# 03_MotorStage_v1.net
KiCad netlist of a schematic drawn in EAGLE
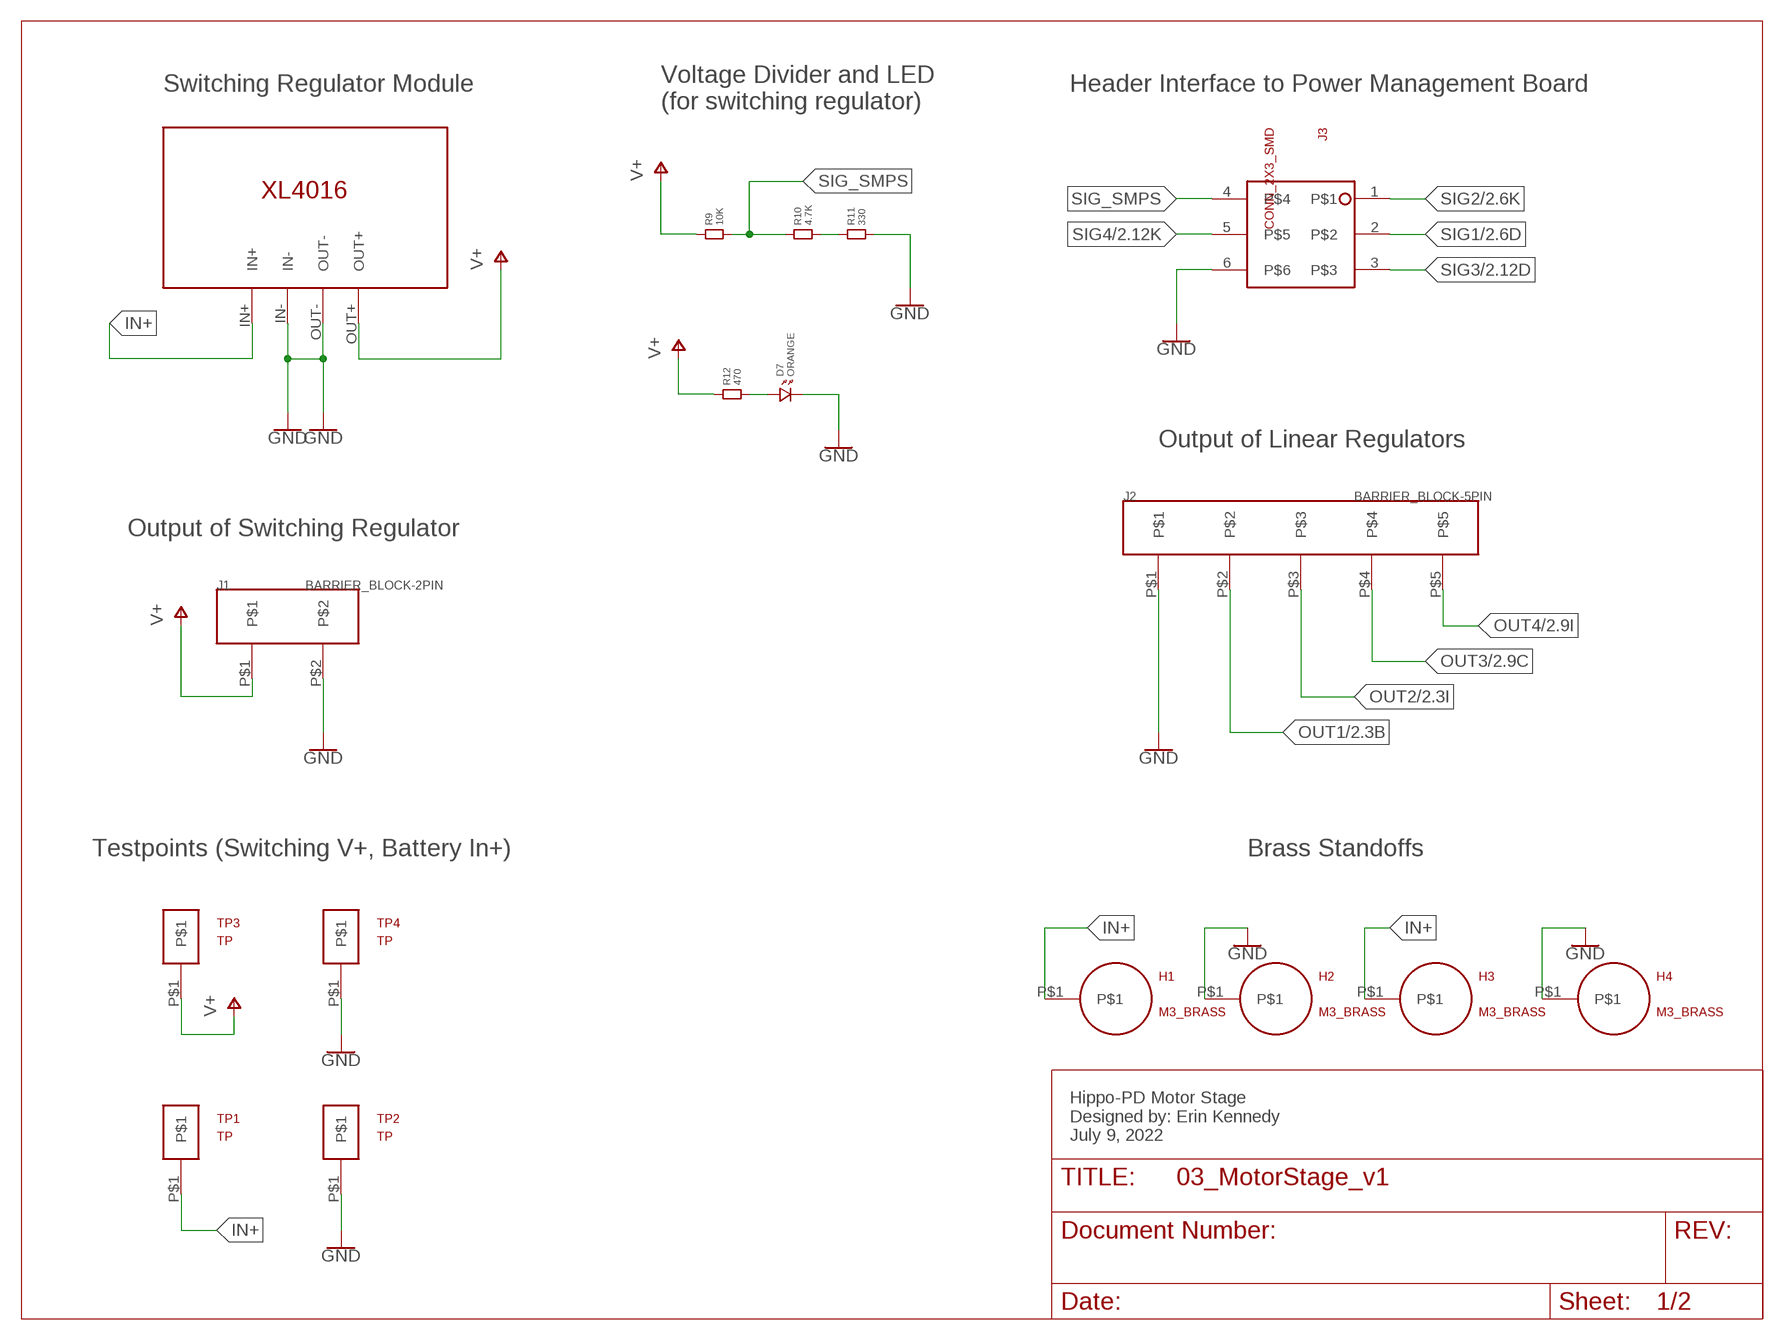
[diagram p0: schematic, sheet 1]
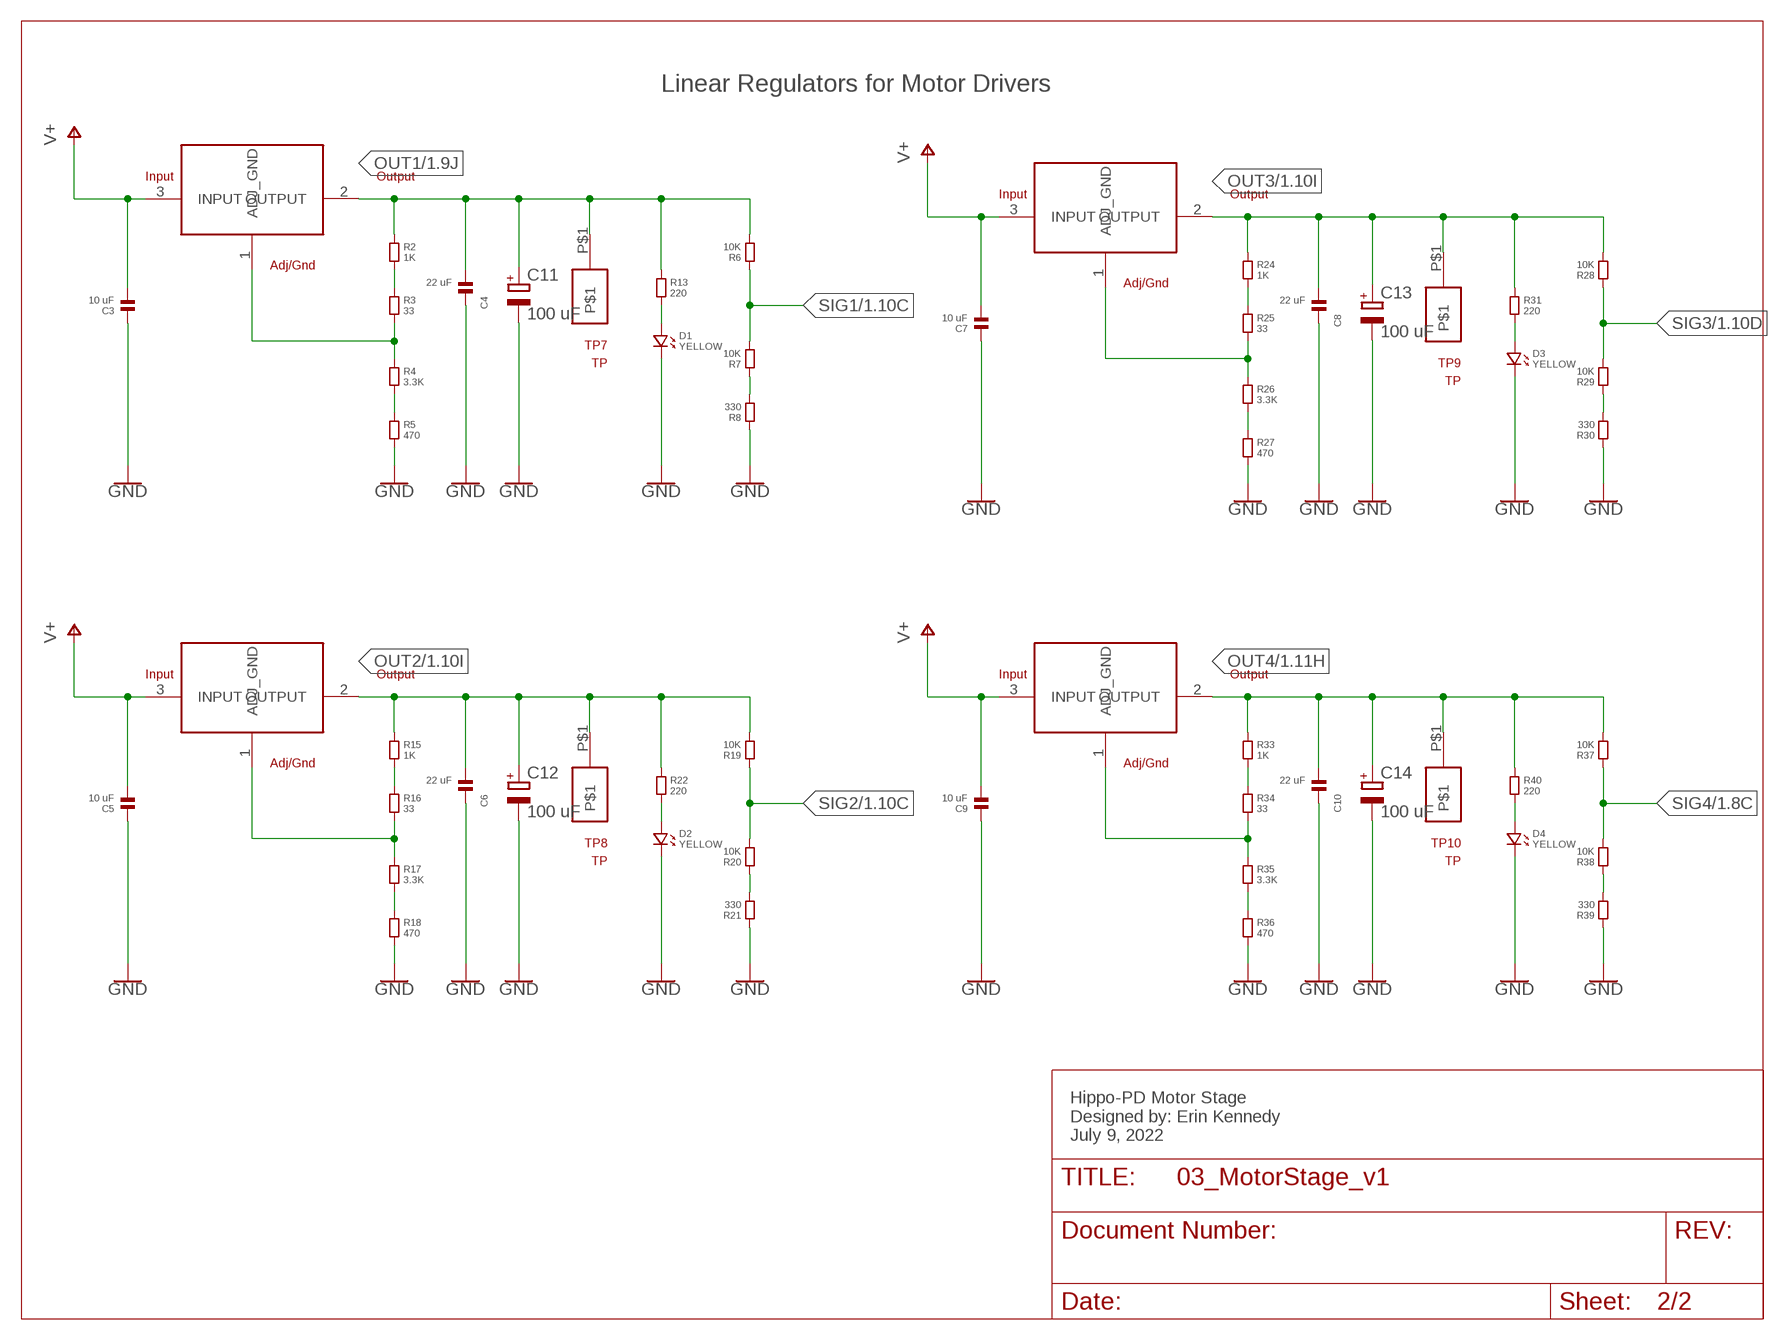
[diagram p1: schematic, sheet 2]

(export (version "E")
  (design (tool "Eeschema 10.0.6"))
  (components
    (comp (ref "C3")
      (value "10 uF")
      (footprint "eagle-import:1206")
      (libsource (lib "eagle-import") (part "CAPACITOR.1206"))
    )
    (comp (ref "C4")
      (value "22 uF")
      (footprint "eagle-import:1206")
      (libsource (lib "eagle-import") (part "CAPACITOR.1206"))
    )
    (comp (ref "C5")
      (value "10 uF")
      (footprint "eagle-import:1206")
      (libsource (lib "eagle-import") (part "CAPACITOR.1206"))
    )
    (comp (ref "C6")
      (value "22 uF")
      (footprint "eagle-import:1206")
      (libsource (lib "eagle-import") (part "CAPACITOR.1206"))
    )
    (comp (ref "C7")
      (value "10 uF")
      (footprint "eagle-import:1206")
      (libsource (lib "eagle-import") (part "CAPACITOR.1206"))
    )
    (comp (ref "C8")
      (value "22 uF")
      (footprint "eagle-import:1206")
      (libsource (lib "eagle-import") (part "CAPACITOR.1206"))
    )
    (comp (ref "C9")
      (value "10 uF")
      (footprint "eagle-import:1206")
      (libsource (lib "eagle-import") (part "CAPACITOR.1206"))
    )
    (comp (ref "C10")
      (value "22 uF")
      (footprint "eagle-import:1206")
      (libsource (lib "eagle-import") (part "CAPACITOR.1206"))
    )
    (comp (ref "C11")
      (value "100 uF")
      (footprint "eagle-import:ELECTROLYTIC_CAP")
      (fields (field (name "MF") "Wurth Electronics") (field (name "MP") "865080545012"))
      (libsource (lib "eagle-import") (part "ELECTROLYTIC_CAP"))
    )
    (comp (ref "C12")
      (value "100 uF")
      (footprint "eagle-import:ELECTROLYTIC_CAP")
      (fields (field (name "MF") "Wurth Electronics") (field (name "MP") "865080545012"))
      (libsource (lib "eagle-import") (part "ELECTROLYTIC_CAP"))
    )
    (comp (ref "C13")
      (value "100 uF")
      (footprint "eagle-import:ELECTROLYTIC_CAP")
      (fields (field (name "MF") "Wurth Electronics") (field (name "MP") "865080545012"))
      (libsource (lib "eagle-import") (part "ELECTROLYTIC_CAP"))
    )
    (comp (ref "C14")
      (value "100 uF")
      (footprint "eagle-import:ELECTROLYTIC_CAP")
      (fields (field (name "MF") "Wurth Electronics") (field (name "MP") "865080545012"))
      (libsource (lib "eagle-import") (part "ELECTROLYTIC_CAP"))
    )
    (comp (ref "D1")
      (value "YELLOW")
      (footprint "eagle-import:1206.LED")
      (libsource (lib "eagle-import") (part "LED.1206"))
    )
    (comp (ref "D2")
      (value "YELLOW")
      (footprint "eagle-import:1206.LED")
      (libsource (lib "eagle-import") (part "LED.1206"))
    )
    (comp (ref "D3")
      (value "YELLOW")
      (footprint "eagle-import:1206.LED")
      (libsource (lib "eagle-import") (part "LED.1206"))
    )
    (comp (ref "D4")
      (value "YELLOW")
      (footprint "eagle-import:1206.LED")
      (libsource (lib "eagle-import") (part "LED.1206"))
    )
    (comp (ref "R2")
      (value "1K")
      (footprint "eagle-import:1206")
      (libsource (lib "eagle-import") (part "RESISTOR.1206"))
    )
    (comp (ref "R3")
      (value "33")
      (footprint "eagle-import:1206")
      (libsource (lib "eagle-import") (part "RESISTOR.1206"))
    )
    (comp (ref "R4")
      (value "3.3K")
      (footprint "eagle-import:1206")
      (libsource (lib "eagle-import") (part "RESISTOR.1206"))
    )
    (comp (ref "R5")
      (value "470")
      (footprint "eagle-import:1206")
      (libsource (lib "eagle-import") (part "RESISTOR.1206"))
    )
    (comp (ref "R6")
      (value "10K")
      (footprint "eagle-import:1206")
      (libsource (lib "eagle-import") (part "RESISTOR.1206"))
    )
    (comp (ref "R7")
      (value "10K")
      (footprint "eagle-import:1206")
      (libsource (lib "eagle-import") (part "RESISTOR.1206"))
    )
    (comp (ref "R8")
      (value "330")
      (footprint "eagle-import:1206")
      (libsource (lib "eagle-import") (part "RESISTOR.1206"))
    )
    (comp (ref "R13")
      (value "220")
      (footprint "eagle-import:1206")
      (libsource (lib "eagle-import") (part "RESISTOR.1206"))
    )
    (comp (ref "R15")
      (value "1K")
      (footprint "eagle-import:1206")
      (libsource (lib "eagle-import") (part "RESISTOR.1206"))
    )
    (comp (ref "R16")
      (value "33")
      (footprint "eagle-import:1206")
      (libsource (lib "eagle-import") (part "RESISTOR.1206"))
    )
    (comp (ref "R17")
      (value "3.3K")
      (footprint "eagle-import:1206")
      (libsource (lib "eagle-import") (part "RESISTOR.1206"))
    )
    (comp (ref "R18")
      (value "470")
      (footprint "eagle-import:1206")
      (libsource (lib "eagle-import") (part "RESISTOR.1206"))
    )
    (comp (ref "R19")
      (value "10K")
      (footprint "eagle-import:1206")
      (libsource (lib "eagle-import") (part "RESISTOR.1206"))
    )
    (comp (ref "R20")
      (value "10K")
      (footprint "eagle-import:1206")
      (libsource (lib "eagle-import") (part "RESISTOR.1206"))
    )
    (comp (ref "R21")
      (value "330")
      (footprint "eagle-import:1206")
      (libsource (lib "eagle-import") (part "RESISTOR.1206"))
    )
    (comp (ref "R22")
      (value "220")
      (footprint "eagle-import:1206")
      (libsource (lib "eagle-import") (part "RESISTOR.1206"))
    )
    (comp (ref "R24")
      (value "1K")
      (footprint "eagle-import:1206")
      (libsource (lib "eagle-import") (part "RESISTOR.1206"))
    )
    (comp (ref "R25")
      (value "33")
      (footprint "eagle-import:1206")
      (libsource (lib "eagle-import") (part "RESISTOR.1206"))
    )
    (comp (ref "R26")
      (value "3.3K")
      (footprint "eagle-import:1206")
      (libsource (lib "eagle-import") (part "RESISTOR.1206"))
    )
    (comp (ref "R27")
      (value "470")
      (footprint "eagle-import:1206")
      (libsource (lib "eagle-import") (part "RESISTOR.1206"))
    )
    (comp (ref "R28")
      (value "10K")
      (footprint "eagle-import:1206")
      (libsource (lib "eagle-import") (part "RESISTOR.1206"))
    )
    (comp (ref "R29")
      (value "10K")
      (footprint "eagle-import:1206")
      (libsource (lib "eagle-import") (part "RESISTOR.1206"))
    )
    (comp (ref "R30")
      (value "330")
      (footprint "eagle-import:1206")
      (libsource (lib "eagle-import") (part "RESISTOR.1206"))
    )
    (comp (ref "R31")
      (value "220")
      (footprint "eagle-import:1206")
      (libsource (lib "eagle-import") (part "RESISTOR.1206"))
    )
    (comp (ref "R33")
      (value "1K")
      (footprint "eagle-import:1206")
      (libsource (lib "eagle-import") (part "RESISTOR.1206"))
    )
    (comp (ref "R34")
      (value "33")
      (footprint "eagle-import:1206")
      (libsource (lib "eagle-import") (part "RESISTOR.1206"))
    )
    (comp (ref "R35")
      (value "3.3K")
      (footprint "eagle-import:1206")
      (libsource (lib "eagle-import") (part "RESISTOR.1206"))
    )
    (comp (ref "R36")
      (value "470")
      (footprint "eagle-import:1206")
      (libsource (lib "eagle-import") (part "RESISTOR.1206"))
    )
    (comp (ref "R37")
      (value "10K")
      (footprint "eagle-import:1206")
      (libsource (lib "eagle-import") (part "RESISTOR.1206"))
    )
    (comp (ref "R38")
      (value "10K")
      (footprint "eagle-import:1206")
      (libsource (lib "eagle-import") (part "RESISTOR.1206"))
    )
    (comp (ref "R39")
      (value "330")
      (footprint "eagle-import:1206")
      (libsource (lib "eagle-import") (part "RESISTOR.1206"))
    )
    (comp (ref "R40")
      (value "220")
      (footprint "eagle-import:1206")
      (libsource (lib "eagle-import") (part "RESISTOR.1206"))
    )
    (comp (ref "TP7") (value "TP") (footprint "eagle-import:TP") (libsource (lib "eagle-import") (part "TP")))
    (comp (ref "TP8") (value "TP") (footprint "eagle-import:TP") (libsource (lib "eagle-import") (part "TP")))
    (comp (ref "TP9") (value "TP") (footprint "eagle-import:TP") (libsource (lib "eagle-import") (part "TP")))
    (comp (ref "TP10")
      (value "TP")
      (footprint "eagle-import:TP")
      (libsource (lib "eagle-import") (part "TP"))
    )
    (comp (ref "U2")
      (value "AZ1084C")
      (footprint "eagle-import:AZ1084C")
      (libsource (lib "eagle-import") (part "AZ1084C"))
    )
    (comp (ref "U3")
      (value "AZ1084C")
      (footprint "eagle-import:AZ1084C")
      (libsource (lib "eagle-import") (part "AZ1084C"))
    )
    (comp (ref "U4")
      (value "AZ1084C")
      (footprint "eagle-import:AZ1084C")
      (libsource (lib "eagle-import") (part "AZ1084C"))
    )
    (comp (ref "U5")
      (value "AZ1084C")
      (footprint "eagle-import:AZ1084C")
      (libsource (lib "eagle-import") (part "AZ1084C"))
    )
    (comp (ref "D7")
      (value "ORANGE")
      (footprint "eagle-import:1206.LED")
      (libsource (lib "eagle-import") (part "LED.1206"))
    )
    (comp (ref "H1")
      (value "M3_BRASS")
      (footprint "eagle-import:M3_BRASS")
      (libsource (lib "eagle-import") (part "M3_BRASS"))
    )
    (comp (ref "H2")
      (value "M3_BRASS")
      (footprint "eagle-import:M3_BRASS")
      (libsource (lib "eagle-import") (part "M3_BRASS"))
    )
    (comp (ref "H3")
      (value "M3_BRASS")
      (footprint "eagle-import:M3_BRASS")
      (libsource (lib "eagle-import") (part "M3_BRASS"))
    )
    (comp (ref "H4")
      (value "M3_BRASS")
      (footprint "eagle-import:M3_BRASS")
      (libsource (lib "eagle-import") (part "M3_BRASS"))
    )
    (comp (ref "J1")
      (value "BARRIER_BLOCK-2PIN")
      (footprint "eagle-import:BARRIERBLOCK-2PIN")
      (libsource (lib "eagle-import") (part "BARRIER_BLOCK-2PIN"))
    )
    (comp (ref "J2")
      (value "BARRIER_BLOCK-5PIN")
      (footprint "eagle-import:BARRIERBLOCK-5PIN")
      (libsource (lib "eagle-import") (part "BARRIER_BLOCK-5PIN"))
    )
    (comp (ref "J3")
      (value "CONN_2X3_SMD")
      (footprint "eagle-import:2X3_SMD_CONNECTOR")
      (libsource (lib "eagle-import") (part "CONN_2X3_SMD"))
    )
    (comp (ref "R9")
      (value "10K")
      (footprint "eagle-import:1206")
      (libsource (lib "eagle-import") (part "RESISTOR.1206"))
    )
    (comp (ref "R10")
      (value "4.7K")
      (footprint "eagle-import:1206")
      (libsource (lib "eagle-import") (part "RESISTOR.1206"))
    )
    (comp (ref "R11")
      (value "330")
      (footprint "eagle-import:1206")
      (libsource (lib "eagle-import") (part "RESISTOR.1206"))
    )
    (comp (ref "R12")
      (value "470")
      (footprint "eagle-import:1206")
      (libsource (lib "eagle-import") (part "RESISTOR.1206"))
    )
    (comp (ref "TP1") (value "TP") (footprint "eagle-import:TP") (libsource (lib "eagle-import") (part "TP")))
    (comp (ref "TP2") (value "TP") (footprint "eagle-import:TP") (libsource (lib "eagle-import") (part "TP")))
    (comp (ref "TP3") (value "TP") (footprint "eagle-import:TP") (libsource (lib "eagle-import") (part "TP")))
    (comp (ref "TP4") (value "TP") (footprint "eagle-import:TP") (libsource (lib "eagle-import") (part "TP")))
    (comp (ref "U1")
      (value "XL4016-DEV")
      (footprint "eagle-import:XL4016-DEV")
      (libsource (lib "eagle-import") (part "XL4016-DEV"))
    )
  )
  (nets
    (net (code "1") (name "GND") (class "Default")
      (node (ref "C10") (pin "1") (pinfunction "1_1") (pintype "bidirectional"))
      (node (ref "C11") (pin "-") (pinfunction "-_-") (pintype "passive"))
      (node (ref "C12") (pin "-") (pinfunction "-_-") (pintype "passive"))
      (node (ref "C13") (pin "-") (pinfunction "-_-") (pintype "passive"))
      (node (ref "C14") (pin "-") (pinfunction "-_-") (pintype "passive"))
      (node (ref "C3") (pin "1") (pinfunction "1_1") (pintype "bidirectional"))
      (node (ref "C4") (pin "1") (pinfunction "1_1") (pintype "bidirectional"))
      (node (ref "C5") (pin "1") (pinfunction "1_1") (pintype "bidirectional"))
      (node (ref "C6") (pin "1") (pinfunction "1_1") (pintype "bidirectional"))
      (node (ref "C7") (pin "1") (pinfunction "1_1") (pintype "bidirectional"))
      (node (ref "C8") (pin "1") (pinfunction "1_1") (pintype "bidirectional"))
      (node (ref "C9") (pin "1") (pinfunction "1_1") (pintype "bidirectional"))
      (node (ref "D1") (pin "P$2") (pinfunction "2_P$2") (pintype "bidirectional"))
      (node (ref "D2") (pin "P$2") (pinfunction "2_P$2") (pintype "bidirectional"))
      (node (ref "D3") (pin "P$2") (pinfunction "2_P$2") (pintype "bidirectional"))
      (node (ref "D4") (pin "P$2") (pinfunction "2_P$2") (pintype "bidirectional"))
      (node (ref "D7") (pin "P$2") (pinfunction "2_P$2") (pintype "bidirectional"))
      (node (ref "H2") (pin "P$1") (pinfunction "P$1_P$1") (pintype "bidirectional"))
      (node (ref "H4") (pin "P$1") (pinfunction "P$1_P$1") (pintype "bidirectional"))
      (node (ref "J1") (pin "P$2") (pinfunction "P$2_P$2") (pintype "bidirectional"))
      (node (ref "J2") (pin "P$1") (pinfunction "P$1_P$1") (pintype "bidirectional"))
      (node (ref "J3") (pin "6") (pinfunction "P$6_6") (pintype "bidirectional"))
      (node (ref "R11") (pin "2") (pinfunction "2_2") (pintype "bidirectional"))
      (node (ref "R18") (pin "2") (pinfunction "2_2") (pintype "bidirectional"))
      (node (ref "R21") (pin "1") (pinfunction "1_1") (pintype "bidirectional"))
      (node (ref "R27") (pin "2") (pinfunction "2_2") (pintype "bidirectional"))
      (node (ref "R30") (pin "1") (pinfunction "1_1") (pintype "bidirectional"))
      (node (ref "R36") (pin "2") (pinfunction "2_2") (pintype "bidirectional"))
      (node (ref "R39") (pin "1") (pinfunction "1_1") (pintype "bidirectional"))
      (node (ref "R5") (pin "2") (pinfunction "2_2") (pintype "bidirectional"))
      (node (ref "R8") (pin "1") (pinfunction "1_1") (pintype "bidirectional"))
      (node (ref "TP2") (pin "P$1") (pinfunction "P$1_P$1") (pintype "bidirectional"))
      (node (ref "TP4") (pin "P$1") (pinfunction "P$1_P$1") (pintype "bidirectional"))
      (node (ref "U1") (pin "IN-") (pinfunction "IN-_IN-") (pintype "bidirectional"))
      (node (ref "U1") (pin "OUT-") (pinfunction "OUT-_OUT-") (pintype "bidirectional"))
    )
    (net (code "2") (name "IN+") (class "Default")
      (node (ref "H1") (pin "P$1") (pinfunction "P$1_P$1") (pintype "bidirectional"))
      (node (ref "H3") (pin "P$1") (pinfunction "P$1_P$1") (pintype "bidirectional"))
      (node (ref "TP1") (pin "P$1") (pinfunction "P$1_P$1") (pintype "bidirectional"))
      (node (ref "U1") (pin "IN+") (pinfunction "IN+_IN+") (pintype "bidirectional"))
    )
    (net (code "3") (name "Net-(D1-1)") (class "Default")
      (node (ref "D1") (pin "P$1") (pinfunction "1_P$1") (pintype "bidirectional"))
      (node (ref "R13") (pin "2") (pinfunction "2_2") (pintype "bidirectional"))
    )
    (net (code "4") (name "Net-(D2-1)") (class "Default")
      (node (ref "D2") (pin "P$1") (pinfunction "1_P$1") (pintype "bidirectional"))
      (node (ref "R22") (pin "2") (pinfunction "2_2") (pintype "bidirectional"))
    )
    (net (code "5") (name "Net-(D3-1)") (class "Default")
      (node (ref "D3") (pin "P$1") (pinfunction "1_P$1") (pintype "bidirectional"))
      (node (ref "R31") (pin "2") (pinfunction "2_2") (pintype "bidirectional"))
    )
    (net (code "6") (name "Net-(D4-1)") (class "Default")
      (node (ref "D4") (pin "P$1") (pinfunction "1_P$1") (pintype "bidirectional"))
      (node (ref "R40") (pin "2") (pinfunction "2_2") (pintype "bidirectional"))
    )
    (net (code "7") (name "Net-(D7-1)") (class "Default")
      (node (ref "D7") (pin "P$1") (pinfunction "1_P$1") (pintype "bidirectional"))
      (node (ref "R12") (pin "2") (pinfunction "2_2") (pintype "bidirectional"))
    )
    (net (code "8") (name "Net-(R2-Pad2)") (class "Default")
      (node (ref "R2") (pin "2") (pinfunction "2_2") (pintype "bidirectional"))
      (node (ref "R3") (pin "1") (pinfunction "1_1") (pintype "bidirectional"))
    )
    (net (code "9") (name "Net-(R4-Pad2)") (class "Default")
      (node (ref "R4") (pin "2") (pinfunction "2_2") (pintype "bidirectional"))
      (node (ref "R5") (pin "1") (pinfunction "1_1") (pintype "bidirectional"))
    )
    (net (code "10") (name "Net-(R7-Pad1)") (class "Default")
      (node (ref "R7") (pin "1") (pinfunction "1_1") (pintype "bidirectional"))
      (node (ref "R8") (pin "2") (pinfunction "2_2") (pintype "bidirectional"))
    )
    (net (code "11") (name "Net-(R10-Pad2)") (class "Default")
      (node (ref "R10") (pin "2") (pinfunction "2_2") (pintype "bidirectional"))
      (node (ref "R11") (pin "1") (pinfunction "1_1") (pintype "bidirectional"))
    )
    (net (code "12") (name "Net-(R15-Pad2)") (class "Default")
      (node (ref "R15") (pin "2") (pinfunction "2_2") (pintype "bidirectional"))
      (node (ref "R16") (pin "1") (pinfunction "1_1") (pintype "bidirectional"))
    )
    (net (code "13") (name "Net-(R17-Pad2)") (class "Default")
      (node (ref "R17") (pin "2") (pinfunction "2_2") (pintype "bidirectional"))
      (node (ref "R18") (pin "1") (pinfunction "1_1") (pintype "bidirectional"))
    )
    (net (code "14") (name "Net-(R20-Pad1)") (class "Default")
      (node (ref "R20") (pin "1") (pinfunction "1_1") (pintype "bidirectional"))
      (node (ref "R21") (pin "2") (pinfunction "2_2") (pintype "bidirectional"))
    )
    (net (code "15") (name "Net-(R24-Pad2)") (class "Default")
      (node (ref "R24") (pin "2") (pinfunction "2_2") (pintype "bidirectional"))
      (node (ref "R25") (pin "1") (pinfunction "1_1") (pintype "bidirectional"))
    )
    (net (code "16") (name "Net-(R26-Pad2)") (class "Default")
      (node (ref "R26") (pin "2") (pinfunction "2_2") (pintype "bidirectional"))
      (node (ref "R27") (pin "1") (pinfunction "1_1") (pintype "bidirectional"))
    )
    (net (code "17") (name "Net-(R29-Pad1)") (class "Default")
      (node (ref "R29") (pin "1") (pinfunction "1_1") (pintype "bidirectional"))
      (node (ref "R30") (pin "2") (pinfunction "2_2") (pintype "bidirectional"))
    )
    (net (code "18") (name "Net-(R33-Pad2)") (class "Default")
      (node (ref "R33") (pin "2") (pinfunction "2_2") (pintype "bidirectional"))
      (node (ref "R34") (pin "1") (pinfunction "1_1") (pintype "bidirectional"))
    )
    (net (code "19") (name "Net-(R35-Pad2)") (class "Default")
      (node (ref "R35") (pin "2") (pinfunction "2_2") (pintype "bidirectional"))
      (node (ref "R36") (pin "1") (pinfunction "1_1") (pintype "bidirectional"))
    )
    (net (code "20") (name "Net-(R38-Pad1)") (class "Default")
      (node (ref "R38") (pin "1") (pinfunction "1_1") (pintype "bidirectional"))
      (node (ref "R39") (pin "2") (pinfunction "2_2") (pintype "bidirectional"))
    )
    (net (code "21") (name "Net-(U2-ADJ_GND)") (class "Default")
      (node (ref "R3") (pin "2") (pinfunction "2_2") (pintype "bidirectional"))
      (node (ref "R4") (pin "1") (pinfunction "1_1") (pintype "bidirectional"))
      (node (ref "U2") (pin "1") (pinfunction "ADJ_GND_1") (pintype "bidirectional"))
    )
    (net (code "22") (name "Net-(U3-ADJ_GND)") (class "Default")
      (node (ref "R16") (pin "2") (pinfunction "2_2") (pintype "bidirectional"))
      (node (ref "R17") (pin "1") (pinfunction "1_1") (pintype "bidirectional"))
      (node (ref "U3") (pin "1") (pinfunction "ADJ_GND_1") (pintype "bidirectional"))
    )
    (net (code "23") (name "Net-(U4-ADJ_GND)") (class "Default")
      (node (ref "R25") (pin "2") (pinfunction "2_2") (pintype "bidirectional"))
      (node (ref "R26") (pin "1") (pinfunction "1_1") (pintype "bidirectional"))
      (node (ref "U4") (pin "1") (pinfunction "ADJ_GND_1") (pintype "bidirectional"))
    )
    (net (code "24") (name "Net-(U5-ADJ_GND)") (class "Default")
      (node (ref "R34") (pin "2") (pinfunction "2_2") (pintype "bidirectional"))
      (node (ref "R35") (pin "1") (pinfunction "1_1") (pintype "bidirectional"))
      (node (ref "U5") (pin "1") (pinfunction "ADJ_GND_1") (pintype "bidirectional"))
    )
    (net (code "25") (name "OUT1") (class "Default")
      (node (ref "C11") (pin "+") (pinfunction "+_+") (pintype "passive"))
      (node (ref "C4") (pin "2") (pinfunction "2_2") (pintype "bidirectional"))
      (node (ref "J2") (pin "P$2") (pinfunction "P$2_P$2") (pintype "bidirectional"))
      (node (ref "R13") (pin "1") (pinfunction "1_1") (pintype "bidirectional"))
      (node (ref "R2") (pin "1") (pinfunction "1_1") (pintype "bidirectional"))
      (node (ref "R6") (pin "2") (pinfunction "2_2") (pintype "bidirectional"))
      (node (ref "TP7") (pin "P$1") (pinfunction "P$1_P$1") (pintype "bidirectional"))
      (node (ref "U2") (pin "2") (pinfunction "OUTPUT_2") (pintype "bidirectional"))
    )
    (net (code "26") (name "OUT2") (class "Default")
      (node (ref "C12") (pin "+") (pinfunction "+_+") (pintype "passive"))
      (node (ref "C6") (pin "2") (pinfunction "2_2") (pintype "bidirectional"))
      (node (ref "J2") (pin "P$3") (pinfunction "P$3_P$3") (pintype "bidirectional"))
      (node (ref "R15") (pin "1") (pinfunction "1_1") (pintype "bidirectional"))
      (node (ref "R19") (pin "2") (pinfunction "2_2") (pintype "bidirectional"))
      (node (ref "R22") (pin "1") (pinfunction "1_1") (pintype "bidirectional"))
      (node (ref "TP8") (pin "P$1") (pinfunction "P$1_P$1") (pintype "bidirectional"))
      (node (ref "U3") (pin "2") (pinfunction "OUTPUT_2") (pintype "bidirectional"))
    )
    (net (code "27") (name "OUT3") (class "Default")
      (node (ref "C13") (pin "+") (pinfunction "+_+") (pintype "passive"))
      (node (ref "C8") (pin "2") (pinfunction "2_2") (pintype "bidirectional"))
      (node (ref "J2") (pin "P$4") (pinfunction "P$4_P$4") (pintype "bidirectional"))
      (node (ref "R24") (pin "1") (pinfunction "1_1") (pintype "bidirectional"))
      (node (ref "R28") (pin "2") (pinfunction "2_2") (pintype "bidirectional"))
      (node (ref "R31") (pin "1") (pinfunction "1_1") (pintype "bidirectional"))
      (node (ref "TP9") (pin "P$1") (pinfunction "P$1_P$1") (pintype "bidirectional"))
      (node (ref "U4") (pin "2") (pinfunction "OUTPUT_2") (pintype "bidirectional"))
    )
    (net (code "28") (name "OUT4") (class "Default")
      (node (ref "C10") (pin "2") (pinfunction "2_2") (pintype "bidirectional"))
      (node (ref "C14") (pin "+") (pinfunction "+_+") (pintype "passive"))
      (node (ref "J2") (pin "P$5") (pinfunction "P$5_P$5") (pintype "bidirectional"))
      (node (ref "R33") (pin "1") (pinfunction "1_1") (pintype "bidirectional"))
      (node (ref "R37") (pin "2") (pinfunction "2_2") (pintype "bidirectional"))
      (node (ref "R40") (pin "1") (pinfunction "1_1") (pintype "bidirectional"))
      (node (ref "TP10") (pin "P$1") (pinfunction "P$1_P$1") (pintype "bidirectional"))
      (node (ref "U5") (pin "2") (pinfunction "OUTPUT_2") (pintype "bidirectional"))
    )
    (net (code "29") (name "SIG1") (class "Default")
      (node (ref "J3") (pin "2") (pinfunction "P$2_2") (pintype "bidirectional"))
      (node (ref "R6") (pin "1") (pinfunction "1_1") (pintype "bidirectional"))
      (node (ref "R7") (pin "2") (pinfunction "2_2") (pintype "bidirectional"))
    )
    (net (code "30") (name "SIG2") (class "Default")
      (node (ref "J3") (pin "1") (pinfunction "P$1_1") (pintype "bidirectional"))
      (node (ref "R19") (pin "1") (pinfunction "1_1") (pintype "bidirectional"))
      (node (ref "R20") (pin "2") (pinfunction "2_2") (pintype "bidirectional"))
    )
    (net (code "31") (name "SIG3") (class "Default")
      (node (ref "J3") (pin "3") (pinfunction "P$3_3") (pintype "bidirectional"))
      (node (ref "R28") (pin "1") (pinfunction "1_1") (pintype "bidirectional"))
      (node (ref "R29") (pin "2") (pinfunction "2_2") (pintype "bidirectional"))
    )
    (net (code "32") (name "SIG4") (class "Default")
      (node (ref "J3") (pin "5") (pinfunction "P$5_5") (pintype "bidirectional"))
      (node (ref "R37") (pin "1") (pinfunction "1_1") (pintype "bidirectional"))
      (node (ref "R38") (pin "2") (pinfunction "2_2") (pintype "bidirectional"))
    )
    (net (code "33") (name "SIG_SMPS") (class "Default")
      (node (ref "J3") (pin "4") (pinfunction "P$4_4") (pintype "bidirectional"))
      (node (ref "R10") (pin "1") (pinfunction "1_1") (pintype "bidirectional"))
      (node (ref "R9") (pin "2") (pinfunction "2_2") (pintype "bidirectional"))
    )
    (net (code "34") (name "V+") (class "Default")
      (node (ref "C3") (pin "2") (pinfunction "2_2") (pintype "bidirectional"))
      (node (ref "C5") (pin "2") (pinfunction "2_2") (pintype "bidirectional"))
      (node (ref "C7") (pin "2") (pinfunction "2_2") (pintype "bidirectional"))
      (node (ref "C9") (pin "2") (pinfunction "2_2") (pintype "bidirectional"))
      (node (ref "J1") (pin "P$1") (pinfunction "P$1_P$1") (pintype "bidirectional"))
      (node (ref "R12") (pin "1") (pinfunction "1_1") (pintype "bidirectional"))
      (node (ref "R9") (pin "1") (pinfunction "1_1") (pintype "bidirectional"))
      (node (ref "TP3") (pin "P$1") (pinfunction "P$1_P$1") (pintype "bidirectional"))
      (node (ref "U1") (pin "OUT+") (pinfunction "OUT+_OUT+") (pintype "bidirectional"))
      (node (ref "U2") (pin "3") (pinfunction "INPUT_3") (pintype "bidirectional"))
      (node (ref "U3") (pin "3") (pinfunction "INPUT_3") (pintype "bidirectional"))
      (node (ref "U4") (pin "3") (pinfunction "INPUT_3") (pintype "bidirectional"))
      (node (ref "U5") (pin "3") (pinfunction "INPUT_3") (pintype "bidirectional"))
    )
  )
)
